# SCH_555-timer_2025-10-19.net
KiCad netlist of a schematic drawn in EasyEDA
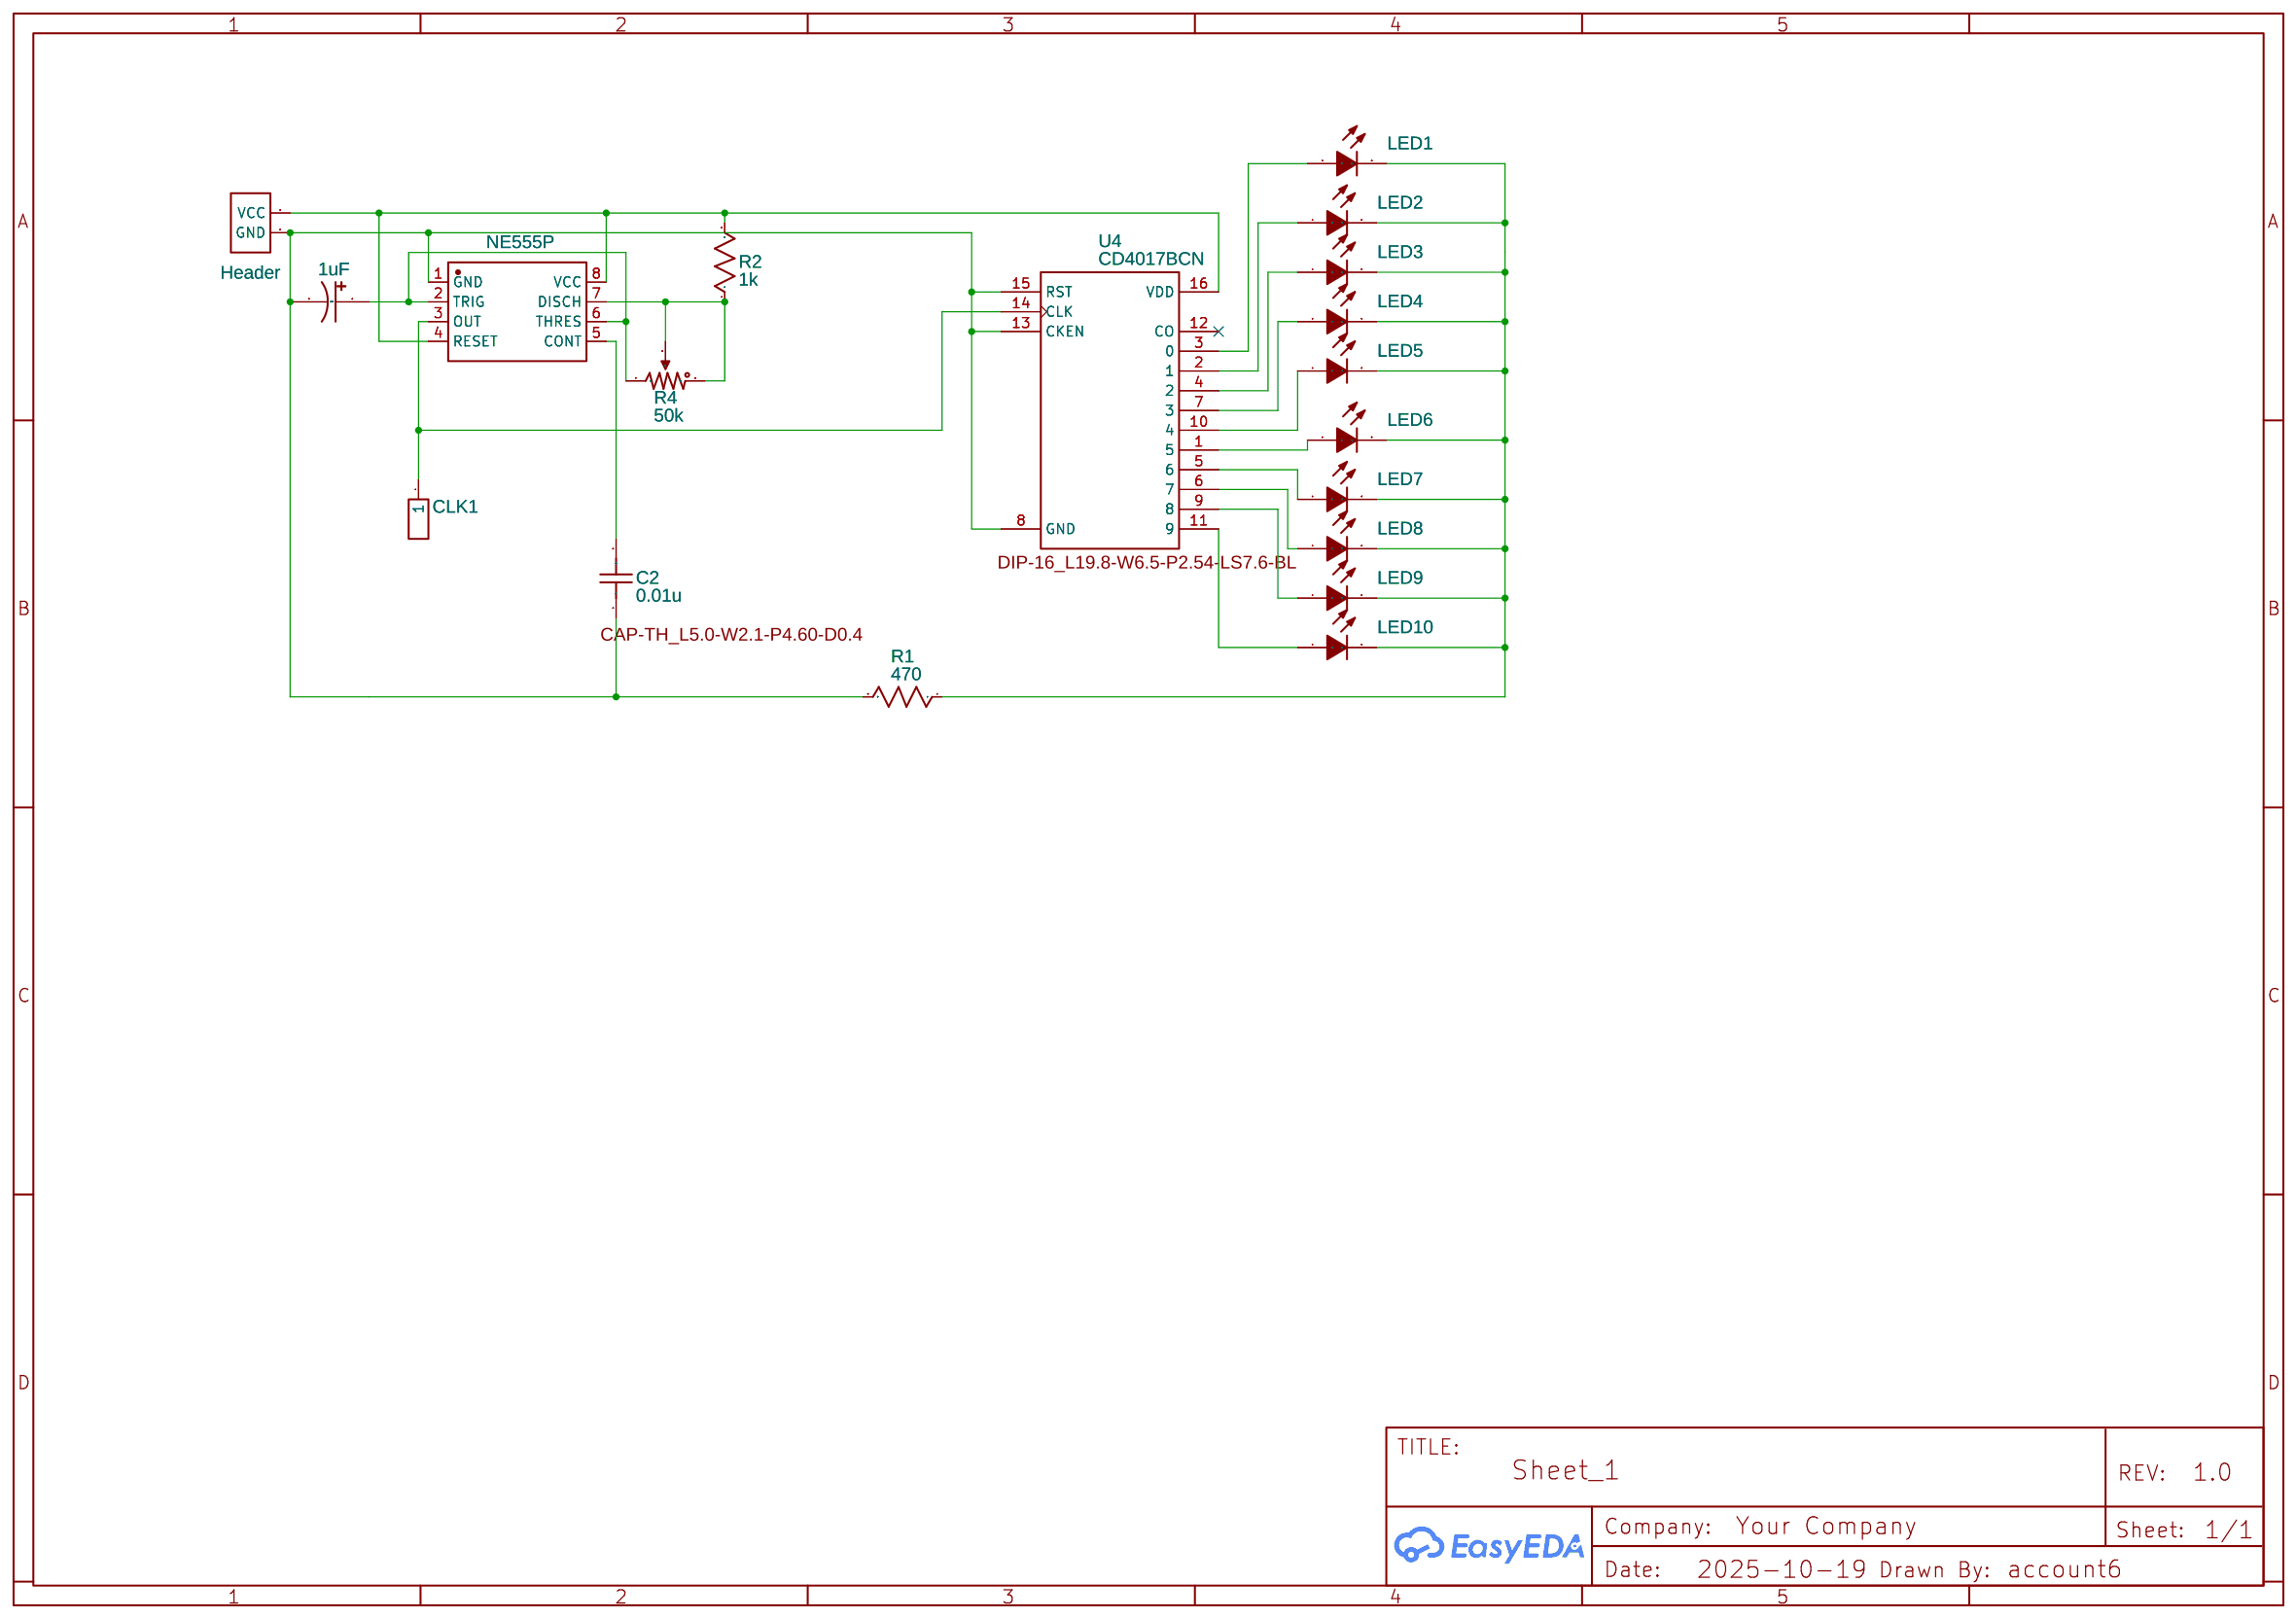
[diagram p0: schematic sheet]

(export (version "E")
  (design (tool "Eeschema 10.0.6"))
  (components
    (comp (ref "C1")
      (value "1uF")
      (fields (field (name "Manufacturer Part") "UVZ1H010MDD") (field (name "Manufacturer") "Nichicon(尼吉康)"))
      (libsource (lib "") (part "UVZ1H010MDD"))
    )
    (comp (ref "C2") (value "0.01u") (libsource (lib "") (part "C_0603_US")))
    (comp (ref "CLK1")
      (value "C81276")
      (fields
        (field (name "Manufacturer Part") "2.54-1*1P针")
        (field (name "Manufacturer") "BOOMELE(Boom Precision Elec)")
      )
      (libsource (lib "") (part "Header-Male-2.54_1x1"))
    )
    (comp (ref "H1") (value "Header") (libsource (lib "") (part "HEADER-FEMALE-2.54_1X2")))
    (comp (ref "LED1") (value "LED_5MM") (libsource (lib "") (part "LED_5MM")))
    (comp (ref "LED2") (value "LED_5MM") (libsource (lib "") (part "LED_5MM")))
    (comp (ref "LED3") (value "LED_5MM") (libsource (lib "") (part "LED_5MM")))
    (comp (ref "LED4") (value "LED_5MM") (libsource (lib "") (part "LED_5MM")))
    (comp (ref "LED5") (value "LED_5MM") (libsource (lib "") (part "LED_5MM")))
    (comp (ref "LED6") (value "LED_5MM") (libsource (lib "") (part "LED_5MM")))
    (comp (ref "LED7") (value "LED_5MM") (libsource (lib "") (part "LED_5MM")))
    (comp (ref "LED8") (value "LED_5MM") (libsource (lib "") (part "LED_5MM")))
    (comp (ref "LED9") (value "LED_5MM") (libsource (lib "") (part "LED_5MM")))
    (comp (ref "LED10") (value "LED_5MM") (libsource (lib "") (part "LED_5MM")))
    (comp (ref "R1")
      (value "470")
      (fields (field (name "Manufacturer Part") "?"))
      (libsource (lib "") (part "Resistor_1"))
    )
    (comp (ref "R2")
      (value "1k")
      (fields (field (name "Manufacturer Part") "?"))
      (libsource (lib "") (part "Resistor"))
    )
    (comp (ref "R4")
      (value "50k")
      (fields (field (name "Manufacturer Part") "?"))
      (libsource (lib "") (part "Potentiometer"))
    )
    (comp (ref "U2")
      (value "NE555P")
      (fields (field (name "Manufacturer") "TI(德州仪器)"))
      (libsource (lib "") (part "NE555P"))
    )
    (comp (ref "U4") (value "CD4017BCN") (libsource (lib "") (part "CD4017BCN")))
  )
  (nets
    (net (code "1") (name "Net-(H1-GND)") (class "Default")
      (node (ref "C1") (pin "2") (pinfunction "2_2") (pintype "unspecified"))
      (node (ref "C2") (pin "1") (pinfunction "1_1") (pintype "unspecified"))
      (node (ref "H1") (pin "2") (pinfunction "GND_2") (pintype "unspecified"))
      (node (ref "R1") (pin "2") (pinfunction "2_2") (pintype "unspecified"))
      (node (ref "U2") (pin "1") (pinfunction "GND_1") (pintype "unspecified"))
      (node (ref "U4") (pin "13") (pinfunction "CKEN_13") (pintype "unspecified"))
      (node (ref "U4") (pin "15") (pinfunction "RST_15") (pintype "unspecified"))
      (node (ref "U4") (pin "8") (pinfunction "GND_8") (pintype "passive"))
    )
    (net (code "2") (name "Net-(H1-VCC)") (class "Default")
      (node (ref "H1") (pin "1") (pinfunction "VCC_1") (pintype "unspecified"))
      (node (ref "R2") (pin "2") (pinfunction "2_2") (pintype "unspecified"))
      (node (ref "U2") (pin "4") (pinfunction "RESET_4") (pintype "unspecified"))
      (node (ref "U2") (pin "8") (pinfunction "VCC_8") (pintype "unspecified"))
      (node (ref "U4") (pin "16") (pinfunction "VDD_16") (pintype "passive"))
    )
    (net (code "3") (name "Net-(LED1-A)") (class "Default")
      (node (ref "LED1") (pin "1") (pinfunction "A_1") (pintype "input"))
      (node (ref "U4") (pin "3") (pinfunction "0_3") (pintype "output"))
    )
    (net (code "4") (name "Net-(LED1-K)") (class "Default")
      (node (ref "LED1") (pin "2") (pinfunction "K_2") (pintype "input"))
      (node (ref "LED10") (pin "2") (pinfunction "K_2") (pintype "input"))
      (node (ref "LED2") (pin "2") (pinfunction "K_2") (pintype "input"))
      (node (ref "LED3") (pin "2") (pinfunction "K_2") (pintype "input"))
      (node (ref "LED4") (pin "2") (pinfunction "K_2") (pintype "input"))
      (node (ref "LED5") (pin "2") (pinfunction "K_2") (pintype "input"))
      (node (ref "LED6") (pin "2") (pinfunction "K_2") (pintype "input"))
      (node (ref "LED7") (pin "2") (pinfunction "K_2") (pintype "input"))
      (node (ref "LED8") (pin "2") (pinfunction "K_2") (pintype "input"))
      (node (ref "LED9") (pin "2") (pinfunction "K_2") (pintype "input"))
      (node (ref "R1") (pin "1") (pinfunction "1_1") (pintype "unspecified"))
    )
    (net (code "5") (name "Net-(LED2-A)") (class "Default")
      (node (ref "LED2") (pin "1") (pinfunction "A_1") (pintype "input"))
      (node (ref "U4") (pin "2") (pinfunction "1_2") (pintype "output"))
    )
    (net (code "6") (name "Net-(LED3-A)") (class "Default")
      (node (ref "LED3") (pin "1") (pinfunction "A_1") (pintype "input"))
      (node (ref "U4") (pin "4") (pinfunction "2_4") (pintype "output"))
    )
    (net (code "7") (name "Net-(LED4-A)") (class "Default")
      (node (ref "LED4") (pin "1") (pinfunction "A_1") (pintype "input"))
      (node (ref "U4") (pin "7") (pinfunction "3_7") (pintype "output"))
    )
    (net (code "8") (name "Net-(LED5-A)") (class "Default")
      (node (ref "LED5") (pin "1") (pinfunction "A_1") (pintype "input"))
      (node (ref "U4") (pin "10") (pinfunction "4_10") (pintype "output"))
    )
    (net (code "9") (name "Net-(LED6-A)") (class "Default")
      (node (ref "LED6") (pin "1") (pinfunction "A_1") (pintype "input"))
      (node (ref "U4") (pin "1") (pinfunction "5_1") (pintype "output"))
    )
    (net (code "10") (name "Net-(LED7-A)") (class "Default")
      (node (ref "LED7") (pin "1") (pinfunction "A_1") (pintype "input"))
      (node (ref "U4") (pin "5") (pinfunction "6_5") (pintype "output"))
    )
    (net (code "11") (name "Net-(LED8-A)") (class "Default")
      (node (ref "LED8") (pin "1") (pinfunction "A_1") (pintype "input"))
      (node (ref "U4") (pin "6") (pinfunction "7_6") (pintype "output"))
    )
    (net (code "12") (name "Net-(LED9-A)") (class "Default")
      (node (ref "LED9") (pin "1") (pinfunction "A_1") (pintype "input"))
      (node (ref "U4") (pin "9") (pinfunction "8_9") (pintype "output"))
    )
    (net (code "13") (name "Net-(LED10-A)") (class "Default")
      (node (ref "LED10") (pin "1") (pinfunction "A_1") (pintype "input"))
      (node (ref "U4") (pin "11") (pinfunction "9_11") (pintype "output"))
    )
    (net (code "14") (name "Net-(R4-2)") (class "Default")
      (node (ref "R2") (pin "1") (pinfunction "1_1") (pintype "unspecified"))
      (node (ref "R4") (pin "2") (pinfunction "3_2") (pintype "unspecified"))
      (node (ref "R4") (pin "3") (pinfunction "2_3") (pintype "unspecified"))
      (node (ref "U2") (pin "7") (pinfunction "DISCH_7") (pintype "unspecified"))
    )
    (net (code "15") (name "Net-(U2-CONT)") (class "Default")
      (node (ref "C2") (pin "2") (pinfunction "2_2") (pintype "unspecified"))
      (node (ref "U2") (pin "5") (pinfunction "CONT_5") (pintype "unspecified"))
    )
    (net (code "16") (name "Net-(U2-OUT)") (class "Default")
      (node (ref "CLK1") (pin "1") (pinfunction "1_1") (pintype "unspecified"))
      (node (ref "U2") (pin "3") (pinfunction "OUT_3") (pintype "unspecified"))
      (node (ref "U4") (pin "14") (pinfunction "CLK_14") (pintype "unspecified"))
    )
    (net (code "17") (name "Net-(U2-THRES)") (class "Default")
      (node (ref "C1") (pin "1") (pinfunction "1_1") (pintype "unspecified"))
      (node (ref "R4") (pin "1") (pinfunction "1_1") (pintype "unspecified"))
      (node (ref "U2") (pin "2") (pinfunction "TRIG_2") (pintype "unspecified"))
      (node (ref "U2") (pin "6") (pinfunction "THRES_6") (pintype "unspecified"))
    )
    (net (code "18") (name "unconnected-(U4-CO-Pad12)") (class "Default")
      (node (ref "U4") (pin "12") (pinfunction "CO_12") (pintype "output+no_connect"))
    )
  )
)
